# Power.net
KiCad netlist of a schematic drawn in Altium Designer
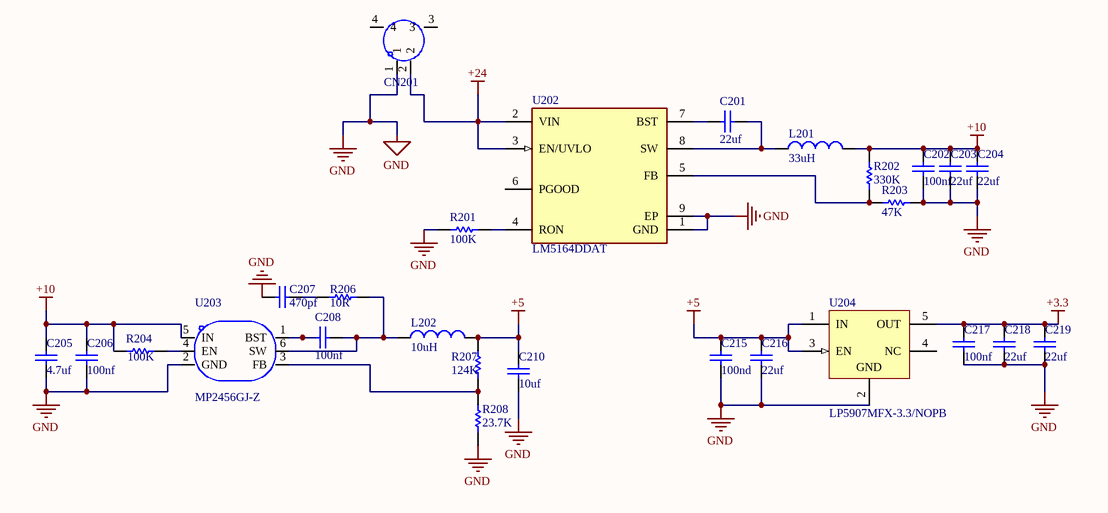
[diagram p0: Power.SchDoc]

(export (version "E")
  (design (tool "Eeschema 10.0.6"))
  (components
    (comp (ref "C201")
      (value "22uf")
      (footprint "CAPC1608X90X35NL10T15")
      (fields (field (name "PART NUMBER") "GRM188R60J106ME47D") (field (name "MANUFACTURER") "Murata"))
      (libsource (lib "Altium Content Vault") (part "CAP"))
    )
    (comp (ref "C202")
      (value "100nf")
      (footprint "CAPC0805(2012)145_N")
      (description "CAP 220nF 50V ±10% 0805 (2012 Metric) Thickness 1.45mm SMD")
      (fields (field (name "TOLERANCE") "Â±10%"))
      (libsource (lib "Altium Content Vault") (part "CAP"))
    )
    (comp (ref "C203")
      (value "22uf")
      (footprint "CAPC0805(2012)145_N")
      (description "CAP 220nF 50V ±10% 0805 (2012 Metric) Thickness 1.45mm SMD")
      (fields (field (name "TOLERANCE") "Â±10%"))
      (libsource (lib "Altium Content Vault") (part "CAP"))
    )
    (comp (ref "C204")
      (value "22uf")
      (footprint "CAPC0805(2012)145_N")
      (description "CAP 220nF 50V ±10% 0805 (2012 Metric) Thickness 1.45mm SMD")
      (fields (field (name "TOLERANCE") "Â±10%"))
      (libsource (lib "Altium Content Vault") (part "CAP"))
    )
    (comp (ref "C205")
      (value "4.7uf")
      (footprint "CAPC1608X87X35ML15T15")
      (fields (field (name "MANUFACTURER") "Kemet") (field (name "PART NUMBER") "C0603C103K5RAC7867"))
      (libsource (lib "Altium Content Vault") (part "CAP"))
    )
    (comp (ref "C206")
      (value "100nf")
      (footprint "CAPC1608X87X35ML15T15")
      (fields (field (name "MANUFACTURER") "Kemet") (field (name "PART NUMBER") "C0603C103K5RAC7867"))
      (libsource (lib "Altium Content Vault") (part "CAP"))
    )
    (comp (ref "C207")
      (value "470pf")
      (footprint "CAPC1608X87X35ML15T15")
      (fields (field (name "MANUFACTURER") "Kemet") (field (name "PART NUMBER") "C0603C103K5RAC7867"))
      (libsource (lib "Altium Content Vault") (part "CAP"))
    )
    (comp (ref "C208")
      (value "100nf")
      (footprint "CAPC1608X87X35ML15T15")
      (fields (field (name "MANUFACTURER") "Kemet") (field (name "PART NUMBER") "C0603C103K5RAC7867"))
      (libsource (lib "Altium Content Vault") (part "CAP"))
    )
    (comp (ref "C210")
      (value "10uf")
      (footprint "CAPC1608X87X35ML15T15")
      (fields (field (name "MANUFACTURER") "Kemet") (field (name "PART NUMBER") "C0603C103K5RAC7867"))
      (libsource (lib "Altium Content Vault") (part "CAP"))
    )
    (comp (ref "C215")
      (value "100nd")
      (footprint "CAPC1608X87X35ML15T15")
      (fields (field (name "MANUFACTURER") "Kemet") (field (name "PART NUMBER") "C0603C103K5RAC7867"))
      (libsource (lib "Altium Content Vault") (part "CAP"))
    )
    (comp (ref "C216")
      (value "22uf")
      (footprint "CAPC1608X87X35ML15T15")
      (fields (field (name "MANUFACTURER") "Kemet") (field (name "PART NUMBER") "C0603C103K5RAC7867"))
      (libsource (lib "Altium Content Vault") (part "CAP"))
    )
    (comp (ref "C217")
      (value "100nf")
      (footprint "CAPC1608X87X35ML15T15")
      (fields (field (name "MANUFACTURER") "Kemet") (field (name "PART NUMBER") "C0603C103K5RAC7867"))
      (libsource (lib "Altium Content Vault") (part "CAP"))
    )
    (comp (ref "C218")
      (value "22uf")
      (footprint "CAPC1608X87X35ML15T15")
      (fields (field (name "MANUFACTURER") "Kemet") (field (name "PART NUMBER") "C0603C103K5RAC7867"))
      (libsource (lib "Altium Content Vault") (part "CAP"))
    )
    (comp (ref "C219")
      (value "22uf")
      (footprint "CAPC1608X87X35ML15T15")
      (fields (field (name "MANUFACTURER") "Kemet") (field (name "PART NUMBER") "C0603C103K5RAC7867"))
      (libsource (lib "Altium Content Vault") (part "CAP"))
    )
    (comp (ref "CN201")
      (value "XT30PW-M")
      (footprint "CONN-TH_XT30PW-M")
      (fields (field (name "MANUFACTURER") "AMASS(艾迈斯)"))
      (libsource (lib "TX30") (part "XT30PW-M"))
    )
    (comp (ref "L201")
      (value "33uH")
      (footprint "TAYO-IND0315_V")
      (description "SMD Power Inductor, 2.2 uH, +/- 20%, 3 x 3 x 1.5 mm, -25 to 120 degC, Pb-Free, Tape and Reel")
      (fields (field (name "MANUFACTURER") "Taiyo Yuden") (field (name "PARTNUMBER") "NR3015T2R2M"))
      (libsource (lib "Altium Content Vault") (part "TAYO-IND-2"))
    )
    (comp (ref "L202")
      (value "10uH")
      (footprint "TAYO-IND0315_V")
      (description "SMD Power Inductor, 2.2 uH, +/- 20%, 3 x 3 x 1.5 mm, -25 to 120 degC, Pb-Free, Tape and Reel")
      (fields (field (name "MANUFACTURER") "Taiyo Yuden") (field (name "PARTNUMBER") "NR3015T2R2M"))
      (libsource (lib "Altium Content Vault") (part "TAYO-IND-2"))
    )
    (comp (ref "R201")
      (value "100K")
      (footprint "RESC1608X55X25ML10T15")
      (description "Chip Resistor, 0 Ohm, +/- 5%, 0.1 W, -55 to 155 degC, 0603 (1608 Metric), RoHS, Tape and Reel")
      (fields (field (name "TOLERANCE") "5%") (field (name "MANUFACTURER") "Yageo"))
      (libsource (lib "Altium Content Vault") (part "RES-2"))
    )
    (comp (ref "R202")
      (value "330K")
      (footprint "RESC2013X50X30LL20T20")
      (fields (field (name "MANUFACTURER") "Vishay Dale") (field (name "PART NUMBER") "CRCW08050000Z0EA"))
      (libsource (lib "Altium Content Vault") (part "RES"))
    )
    (comp (ref "R203")
      (value "47K")
      (footprint "RESC2013X50X30LL20T20")
      (fields (field (name "MANUFACTURER") "Vishay Dale") (field (name "PART NUMBER") "CRCW08050000Z0EA"))
      (libsource (lib "Altium Content Vault") (part "RES"))
    )
    (comp (ref "R204")
      (value "100K")
      (footprint "RESC1608X55X25ML10T15")
      (description "Chip Resistor, 0 Ohm, +/- 5%, 0.1 W, -55 to 155 degC, 0603 (1608 Metric), RoHS, Tape and Reel")
      (fields (field (name "TOLERANCE") "5%") (field (name "MANUFACTURER") "Yageo"))
      (libsource (lib "Altium Content Vault") (part "RES-2"))
    )
    (comp (ref "R206")
      (value "10R")
      (footprint "RESC1608X55X25ML10T15")
      (description "Chip Resistor, 0 Ohm, +/- 5%, 0.1 W, -55 to 155 degC, 0603 (1608 Metric), RoHS, Tape and Reel")
      (fields (field (name "TOLERANCE") "5%") (field (name "MANUFACTURER") "Yageo"))
      (libsource (lib "Altium Content Vault") (part "RES-2"))
    )
    (comp (ref "R207")
      (value "124K")
      (footprint "RESC1608X55X25ML10T15")
      (description "Chip Resistor, 0 Ohm, +/- 5%, 0.1 W, -55 to 155 degC, 0603 (1608 Metric), RoHS, Tape and Reel")
      (fields (field (name "TOLERANCE") "5%") (field (name "MANUFACTURER") "Yageo"))
      (libsource (lib "Altium Content Vault") (part "RES-2"))
    )
    (comp (ref "R208")
      (value "23.7K")
      (footprint "RESC1608X55X25ML10T15")
      (description "Chip Resistor, 0 Ohm, +/- 5%, 0.1 W, -55 to 155 degC, 0603 (1608 Metric), RoHS, Tape and Reel")
      (fields (field (name "TOLERANCE") "5%") (field (name "MANUFACTURER") "Yageo"))
      (libsource (lib "Altium Content Vault") (part "RES-2"))
    )
    (comp (ref "U202")
      (value "LM5164DDAT")
      (footprint "FP-DDA0008E-MFG")
      (description "IC REG BUCK ADJUSTABLE 1A 8SOPWR")
      (fields
        (field (name "MANUFACTURER") "Texas Instruments")
        (field (name "OCTOPART") "https://octopart.com/lm5164ddat-texas+instruments-96785745")
      )
      (libsource (lib "Altium Content Vault") (part "f1dc55cabb1a030b757b3e48329a724"))
    )
    (comp (ref "U203")
      (value "MP2456GJ-Z")
      (footprint "TSOT-23-6_L2.9-W1.6-P0.95-LS2.8-BR")
      (libsource (lib "MP2456GJ") (part "MP2456GJ-Z"))
    )
    (comp (ref "U204")
      (value "LP5907MFX-3.3/NOPB")
      (footprint "DBV0005A_L")
      (fields (field (name "MANUFACTURER") "Texas Instruments"))
      (libsource (lib "Altium Content Vault") (part "TI-LP5907-SOT-23-5"))
    )
  )
  (nets
    (net (code "1") (name "+3.3") (class "Default")
      (node (ref "C217") (pin "2") (pinfunction "2_2") (pintype "passive"))
      (node (ref "C218") (pin "2") (pinfunction "2_2") (pintype "passive"))
      (node (ref "C219") (pin "2") (pinfunction "2_2") (pintype "passive"))
      (node (ref "U204") (pin "5") (pinfunction "OUT_5") (pintype "power_in"))
    )
    (net (code "2") (name "+5") (class "Default")
      (node (ref "C210") (pin "2") (pinfunction "2_2") (pintype "passive"))
      (node (ref "C215") (pin "2") (pinfunction "2_2") (pintype "passive"))
      (node (ref "C216") (pin "2") (pinfunction "2_2") (pintype "passive"))
      (node (ref "L202") (pin "2") (pinfunction "2_2") (pintype "passive"))
      (node (ref "R207") (pin "1") (pinfunction "1_1") (pintype "passive"))
      (node (ref "U204") (pin "1") (pinfunction "IN_1") (pintype "power_in"))
      (node (ref "U204") (pin "3") (pinfunction "EN_3") (pintype "input"))
    )
    (net (code "3") (name "+10") (class "Default")
      (node (ref "C202") (pin "2") (pinfunction "2_2") (pintype "passive"))
      (node (ref "C203") (pin "2") (pinfunction "2_2") (pintype "passive"))
      (node (ref "C204") (pin "2") (pinfunction "2_2") (pintype "passive"))
      (node (ref "C205") (pin "2") (pinfunction "2_2") (pintype "passive"))
      (node (ref "C206") (pin "2") (pinfunction "2_2") (pintype "passive"))
      (node (ref "L201") (pin "2") (pinfunction "2_2") (pintype "passive"))
      (node (ref "R202") (pin "2") (pinfunction "2_2") (pintype "passive"))
      (node (ref "R204") (pin "1") (pinfunction "1_1") (pintype "passive"))
      (node (ref "U203") (pin "5") (pinfunction "IN_5") (pintype "passive"))
    )
    (net (code "4") (name "+24") (class "Default")
      (node (ref "CN201") (pin "2") (pinfunction "2_2") (pintype "passive"))
      (node (ref "U202") (pin "2") (pinfunction "VIN_2") (pintype "power_in"))
      (node (ref "U202") (pin "3") (pinfunction "EN/UVLO_3") (pintype "input"))
    )
    (net (code "5") (name "GND") (class "Default")
      (node (ref "C202") (pin "1") (pinfunction "1_1") (pintype "passive"))
      (node (ref "C203") (pin "1") (pinfunction "1_1") (pintype "passive"))
      (node (ref "C204") (pin "1") (pinfunction "1_1") (pintype "passive"))
      (node (ref "C205") (pin "1") (pinfunction "1_1") (pintype "passive"))
      (node (ref "C206") (pin "1") (pinfunction "1_1") (pintype "passive"))
      (node (ref "C207") (pin "2") (pinfunction "2_2") (pintype "passive"))
      (node (ref "C210") (pin "1") (pinfunction "1_1") (pintype "passive"))
      (node (ref "C215") (pin "1") (pinfunction "1_1") (pintype "passive"))
      (node (ref "C216") (pin "1") (pinfunction "1_1") (pintype "passive"))
      (node (ref "C217") (pin "1") (pinfunction "1_1") (pintype "passive"))
      (node (ref "C218") (pin "1") (pinfunction "1_1") (pintype "passive"))
      (node (ref "C219") (pin "1") (pinfunction "1_1") (pintype "passive"))
      (node (ref "CN201") (pin "1") (pinfunction "1_1") (pintype "passive"))
      (node (ref "R201") (pin "1") (pinfunction "1_1") (pintype "passive"))
      (node (ref "R203") (pin "2") (pinfunction "2_2") (pintype "passive"))
      (node (ref "R208") (pin "1") (pinfunction "1_1") (pintype "passive"))
      (node (ref "U202") (pin "1") (pinfunction "GND_1") (pintype "power_in"))
      (node (ref "U202") (pin "9") (pinfunction "EP_9") (pintype "power_in"))
      (node (ref "U203") (pin "2") (pinfunction "GND_2") (pintype "passive"))
      (node (ref "U204") (pin "2") (pinfunction "GND_2") (pintype "power_in"))
    )
    (net (code "6") (name "Net-(C207-Pad1)") (class "Default")
      (node (ref "C207") (pin "1") (pinfunction "1_1") (pintype "passive"))
      (node (ref "R206") (pin "1") (pinfunction "1_1") (pintype "passive"))
    )
    (net (code "7") (name "Net-(U202-BST)") (class "Default")
      (node (ref "C201") (pin "1") (pinfunction "1_1") (pintype "passive"))
      (node (ref "U202") (pin "7") (pinfunction "BST_7") (pintype "passive"))
    )
    (net (code "8") (name "Net-(U202-FB)") (class "Default")
      (node (ref "R202") (pin "1") (pinfunction "1_1") (pintype "passive"))
      (node (ref "R203") (pin "1") (pinfunction "1_1") (pintype "passive"))
      (node (ref "U202") (pin "5") (pinfunction "FB_5") (pintype "passive"))
    )
    (net (code "9") (name "Net-(U202-RON)") (class "Default")
      (node (ref "R201") (pin "2") (pinfunction "2_2") (pintype "passive"))
      (node (ref "U202") (pin "4") (pinfunction "RON_4") (pintype "passive"))
    )
    (net (code "10") (name "Net-(U202-SW)") (class "Default")
      (node (ref "C201") (pin "2") (pinfunction "2_2") (pintype "passive"))
      (node (ref "L201") (pin "1") (pinfunction "1_1") (pintype "passive"))
      (node (ref "U202") (pin "8") (pinfunction "SW_8") (pintype "passive"))
    )
    (net (code "11") (name "Net-(U203-BST)") (class "Default")
      (node (ref "C208") (pin "2") (pinfunction "2_2") (pintype "passive"))
      (node (ref "U203") (pin "1") (pinfunction "BST_1") (pintype "passive"))
    )
    (net (code "12") (name "Net-(U203-EN)") (class "Default")
      (node (ref "R204") (pin "2") (pinfunction "2_2") (pintype "passive"))
      (node (ref "U203") (pin "4") (pinfunction "EN_4") (pintype "passive"))
    )
    (net (code "13") (name "Net-(U203-FB)") (class "Default")
      (node (ref "R207") (pin "2") (pinfunction "2_2") (pintype "passive"))
      (node (ref "R208") (pin "2") (pinfunction "2_2") (pintype "passive"))
      (node (ref "U203") (pin "3") (pinfunction "FB_3") (pintype "passive"))
    )
    (net (code "14") (name "Net-(U203-SW)") (class "Default")
      (node (ref "C208") (pin "1") (pinfunction "1_1") (pintype "passive"))
      (node (ref "L202") (pin "1") (pinfunction "1_1") (pintype "passive"))
      (node (ref "R206") (pin "2") (pinfunction "2_2") (pintype "passive"))
      (node (ref "U203") (pin "6") (pinfunction "SW_6") (pintype "passive"))
    )
    (net (code "15") (name "unconnected-(CN201-Pad3)") (class "Default")
      (node (ref "CN201") (pin "3") (pinfunction "3_3") (pintype "passive"))
    )
    (net (code "16") (name "unconnected-(CN201-Pad4)") (class "Default")
      (node (ref "CN201") (pin "4") (pinfunction "4_4") (pintype "passive"))
    )
    (net (code "17") (name "unconnected-(U202-PGOOD-Pad6)") (class "Default")
      (node (ref "U202") (pin "6") (pinfunction "PGOOD_6") (pintype "open_collector"))
    )
    (net (code "18") (name "unconnected-(U204-NC-Pad4)") (class "Default")
      (node (ref "U204") (pin "4") (pinfunction "NC_4") (pintype "passive"))
    )
  )
)
